# Camera.net
KiCad netlist of a schematic drawn in Altium Designer
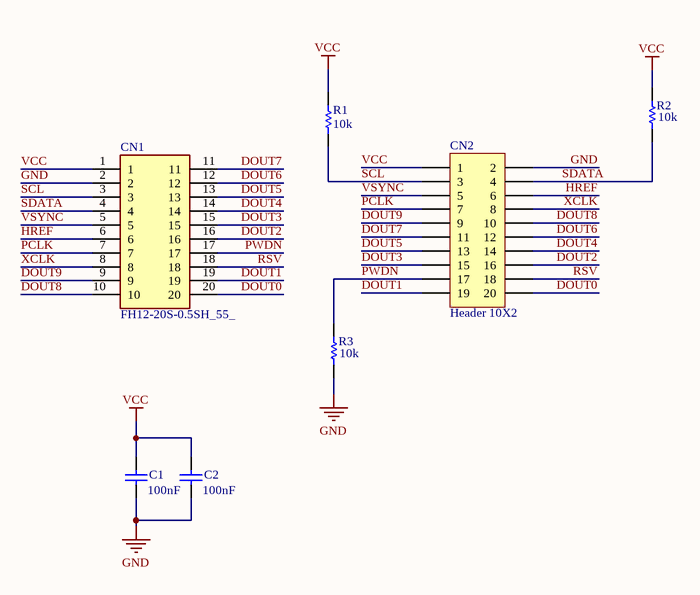
[diagram p0: Camera.SchDoc]

(export (version "E")
  (design (tool "Eeschema 10.0.6"))
  (components
    (comp (ref "C1")
      (value "100nF")
      (footprint "1608[0603]")
      (description "Capacitor")
      (fields (field (name "Comment") "X5R") (field (name "PUBLISHER") "Altium Limited"))
      (libsource (lib "Miscellaneous Devices") (part "Cap"))
    )
    (comp (ref "C2")
      (value "100nF")
      (footprint "1608[0603]")
      (description "Capacitor")
      (fields (field (name "Comment") "X5R") (field (name "PUBLISHER") "Altium Limited"))
      (libsource (lib "Miscellaneous Devices") (part "Cap"))
    )
    (comp (ref "CN1")
      (value "FH12-20S-0.5SH_55_")
      (footprint "SamacSys:FH12-20S-0.5SH(55)")
      (description "Connector")
      (fields
        (field (name "MANUFACTURER_PART_NUMBER") "FH12-20S-0.5SH(55)")
        (field (name "MOUSER PART NUMBER") "798-FH12-20S-0.5SH55")
      )
      (libsource (lib "*") (part "FH12-20S-0.5SH_55_"))
    )
    (comp (ref "CN2")
      (value "Header 10X2")
      (footprint "HDR2X10")
      (description "Header, 10-Pin, Dual row")
      (fields (field (name "PUBLISHER") "Altium Limited"))
      (libsource (lib "Miscellaneous Connectors") (part "Header 10X2"))
    )
    (comp (ref "R1")
      (value "10k")
      (footprint "1608[0603]")
      (description "Resistor")
      (fields (field (name "Comment") "Res1") (field (name "PUBLISHER") "Altium Limited"))
      (libsource (lib "Miscellaneous Devices") (part "Res1"))
    )
    (comp (ref "R2")
      (value "10k")
      (footprint "1608[0603]")
      (description "Resistor")
      (fields (field (name "Comment") "Res1") (field (name "PUBLISHER") "Altium Limited"))
      (libsource (lib "Miscellaneous Devices") (part "Res1"))
    )
    (comp (ref "R3")
      (value "10k")
      (footprint "1608[0603]")
      (description "Resistor")
      (fields (field (name "Comment") "Res1") (field (name "PUBLISHER") "Altium Limited"))
      (libsource (lib "Miscellaneous Devices") (part "Res1"))
    )
  )
  (nets
    (net (code "1") (name "/DOUT0") (class "Default")
      (node (ref "CN1") (pin "20") (pinfunction "20_20") (pintype "passive"))
      (node (ref "CN2") (pin "20") (pinfunction "20_20") (pintype "passive"))
    )
    (net (code "2") (name "/DOUT1") (class "Default")
      (node (ref "CN1") (pin "19") (pinfunction "19_19") (pintype "passive"))
      (node (ref "CN2") (pin "19") (pinfunction "19_19") (pintype "passive"))
    )
    (net (code "3") (name "/DOUT2") (class "Default")
      (node (ref "CN1") (pin "16") (pinfunction "16_16") (pintype "passive"))
      (node (ref "CN2") (pin "16") (pinfunction "16_16") (pintype "passive"))
    )
    (net (code "4") (name "/DOUT3") (class "Default")
      (node (ref "CN1") (pin "15") (pinfunction "15_15") (pintype "passive"))
      (node (ref "CN2") (pin "15") (pinfunction "15_15") (pintype "passive"))
    )
    (net (code "5") (name "/DOUT4") (class "Default")
      (node (ref "CN1") (pin "14") (pinfunction "14_14") (pintype "passive"))
      (node (ref "CN2") (pin "14") (pinfunction "14_14") (pintype "passive"))
    )
    (net (code "6") (name "/DOUT5") (class "Default")
      (node (ref "CN1") (pin "13") (pinfunction "13_13") (pintype "passive"))
      (node (ref "CN2") (pin "13") (pinfunction "13_13") (pintype "passive"))
    )
    (net (code "7") (name "/DOUT6") (class "Default")
      (node (ref "CN1") (pin "12") (pinfunction "12_12") (pintype "passive"))
      (node (ref "CN2") (pin "12") (pinfunction "12_12") (pintype "passive"))
    )
    (net (code "8") (name "/DOUT7") (class "Default")
      (node (ref "CN1") (pin "11") (pinfunction "11_11") (pintype "passive"))
      (node (ref "CN2") (pin "11") (pinfunction "11_11") (pintype "passive"))
    )
    (net (code "9") (name "/DOUT8") (class "Default")
      (node (ref "CN1") (pin "10") (pinfunction "10_10") (pintype "passive"))
      (node (ref "CN2") (pin "10") (pinfunction "10_10") (pintype "passive"))
    )
    (net (code "10") (name "/DOUT9") (class "Default")
      (node (ref "CN1") (pin "9") (pinfunction "9_9") (pintype "passive"))
      (node (ref "CN2") (pin "9") (pinfunction "9_9") (pintype "passive"))
    )
    (net (code "11") (name "/HREF") (class "Default")
      (node (ref "CN1") (pin "6") (pinfunction "6_6") (pintype "passive"))
      (node (ref "CN2") (pin "6") (pinfunction "6_6") (pintype "passive"))
    )
    (net (code "12") (name "/PCLK") (class "Default")
      (node (ref "CN1") (pin "7") (pinfunction "7_7") (pintype "passive"))
      (node (ref "CN2") (pin "7") (pinfunction "7_7") (pintype "passive"))
    )
    (net (code "13") (name "/PWDN") (class "Default")
      (node (ref "CN1") (pin "17") (pinfunction "17_17") (pintype "passive"))
      (node (ref "CN2") (pin "17") (pinfunction "17_17") (pintype "passive"))
      (node (ref "R3") (pin "1") (pinfunction "1_1") (pintype "passive"))
    )
    (net (code "14") (name "/RSV") (class "Default")
      (node (ref "CN1") (pin "18") (pinfunction "18_18") (pintype "passive"))
      (node (ref "CN2") (pin "18") (pinfunction "18_18") (pintype "passive"))
    )
    (net (code "15") (name "/SCL") (class "Default")
      (node (ref "CN1") (pin "3") (pinfunction "3_3") (pintype "passive"))
      (node (ref "CN2") (pin "3") (pinfunction "3_3") (pintype "passive"))
      (node (ref "R1") (pin "2") (pinfunction "2_2") (pintype "passive"))
    )
    (net (code "16") (name "/SDATA") (class "Default")
      (node (ref "CN1") (pin "4") (pinfunction "4_4") (pintype "passive"))
      (node (ref "CN2") (pin "4") (pinfunction "4_4") (pintype "passive"))
      (node (ref "R2") (pin "2") (pinfunction "2_2") (pintype "passive"))
    )
    (net (code "17") (name "/VSYNC") (class "Default")
      (node (ref "CN1") (pin "5") (pinfunction "5_5") (pintype "passive"))
      (node (ref "CN2") (pin "5") (pinfunction "5_5") (pintype "passive"))
    )
    (net (code "18") (name "/XCLK") (class "Default")
      (node (ref "CN1") (pin "8") (pinfunction "8_8") (pintype "passive"))
      (node (ref "CN2") (pin "8") (pinfunction "8_8") (pintype "passive"))
    )
    (net (code "19") (name "GND") (class "Default")
      (node (ref "C1") (pin "2") (pinfunction "2_2") (pintype "passive"))
      (node (ref "C2") (pin "2") (pinfunction "2_2") (pintype "passive"))
      (node (ref "CN1") (pin "2") (pinfunction "2_2") (pintype "passive"))
      (node (ref "CN2") (pin "2") (pinfunction "2_2") (pintype "passive"))
      (node (ref "R3") (pin "2") (pinfunction "2_2") (pintype "passive"))
    )
    (net (code "20") (name "VCC") (class "Default")
      (node (ref "C1") (pin "1") (pinfunction "1_1") (pintype "passive"))
      (node (ref "C2") (pin "1") (pinfunction "1_1") (pintype "passive"))
      (node (ref "CN1") (pin "1") (pinfunction "1_1") (pintype "passive"))
      (node (ref "CN2") (pin "1") (pinfunction "1_1") (pintype "passive"))
      (node (ref "R1") (pin "1") (pinfunction "1_1") (pintype "passive"))
      (node (ref "R2") (pin "1") (pinfunction "1_1") (pintype "passive"))
    )
  )
)
